# M121B.net
KiCad netlist of a schematic drawn in EAGLE
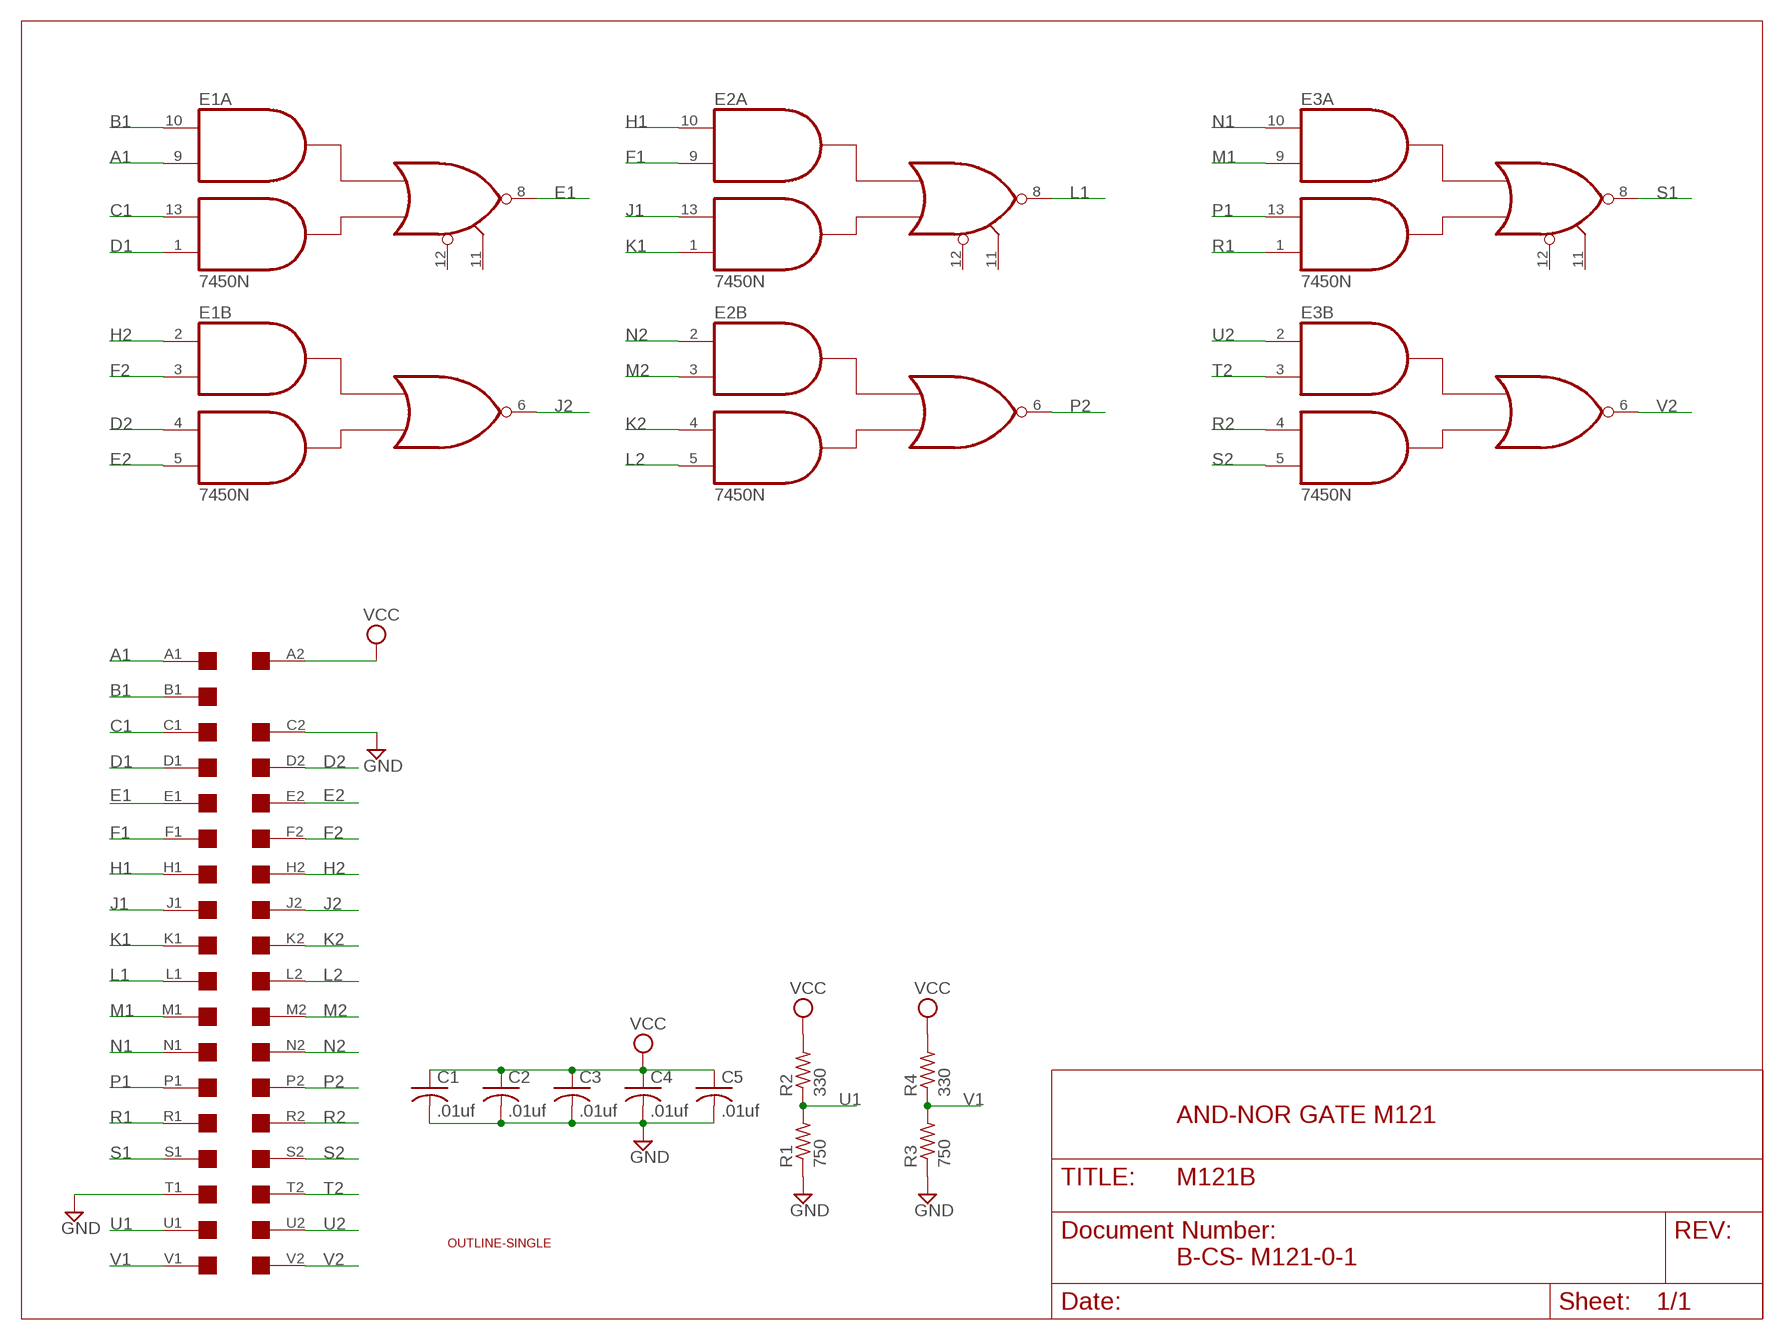
[diagram p0: schematic, sheet 1]

(export (version "E")
  (design (tool "Eeschema 10.0.6"))
  (components
    (comp (ref "C1")
      (value ".01uf")
      (footprint "eagle-import:C050-025X075")
      (libsource (lib "eagle-import") (part "C-US050-025X075"))
    )
    (comp (ref "C2")
      (value ".01uf")
      (footprint "eagle-import:C050-025X075")
      (libsource (lib "eagle-import") (part "C-US050-025X075"))
    )
    (comp (ref "C3")
      (value ".01uf")
      (footprint "eagle-import:C050-025X075")
      (libsource (lib "eagle-import") (part "C-US050-025X075"))
    )
    (comp (ref "C4")
      (value ".01uf")
      (footprint "eagle-import:C050-025X075")
      (libsource (lib "eagle-import") (part "C-US050-025X075"))
    )
    (comp (ref "C5")
      (value ".01uf")
      (footprint "eagle-import:C050-025X075")
      (libsource (lib "eagle-import") (part "C-US050-025X075"))
    )
    (comp (ref "E1")
      (value "7450N")
      (footprint "eagle-import:DIL14")
      (libsource (lib "eagle-import") (part "7450N"))
    )
    (comp (ref "E2")
      (value "7450N")
      (footprint "eagle-import:DIL14")
      (libsource (lib "eagle-import") (part "7450N"))
    )
    (comp (ref "E3")
      (value "7450N")
      (footprint "eagle-import:DIL14")
      (libsource (lib "eagle-import") (part "7450N"))
    )
    (comp (ref "R1")
      (value "750")
      (footprint "eagle-import:0207_10")
      (libsource (lib "eagle-import") (part "R-US_0207/10"))
    )
    (comp (ref "R2")
      (value "330")
      (footprint "eagle-import:0207_10")
      (libsource (lib "eagle-import") (part "R-US_0207/10"))
    )
    (comp (ref "R3")
      (value "750")
      (footprint "eagle-import:0207_10")
      (libsource (lib "eagle-import") (part "R-US_0207/10"))
    )
    (comp (ref "R4")
      (value "330")
      (footprint "eagle-import:0207_10")
      (libsource (lib "eagle-import") (part "R-US_0207/10"))
    )
    (comp (ref "U$1")
      (value "OUTLINE-SINGLE")
      (footprint "eagle-import:SINGLE")
      (libsource (lib "eagle-import") (part "OUTLINE-SINGLE"))
    )
    (comp (ref "U$4")
      (value "SINGLE")
      (footprint "eagle-import:EDGE-CON2")
      (libsource (lib "eagle-import") (part "SINGLE"))
    )
  )
  (nets
    (net (code "1") (name "/A1") (class "Default")
      (node (ref "E1") (pin "9") (pinfunction "I2_9") (pintype "input"))
      (node (ref "U$4") (pin "A1") (pinfunction "1_A1") (pintype "bidirectional"))
    )
    (net (code "2") (name "/B1") (class "Default")
      (node (ref "E1") (pin "10") (pinfunction "I1_10") (pintype "input"))
      (node (ref "U$4") (pin "B1") (pinfunction "1_B1") (pintype "bidirectional"))
    )
    (net (code "3") (name "/C1") (class "Default")
      (node (ref "E1") (pin "13") (pinfunction "I3_13") (pintype "input"))
      (node (ref "U$4") (pin "C1") (pinfunction "1_C1") (pintype "bidirectional"))
    )
    (net (code "4") (name "/D1") (class "Default")
      (node (ref "E1") (pin "1") (pinfunction "I4_1") (pintype "input"))
      (node (ref "U$4") (pin "D1") (pinfunction "1_D1") (pintype "bidirectional"))
    )
    (net (code "5") (name "/D2") (class "Default")
      (node (ref "E1") (pin "4") (pinfunction "I3_4") (pintype "input"))
      (node (ref "U$4") (pin "D2") (pinfunction "1_D2") (pintype "bidirectional"))
    )
    (net (code "6") (name "/E1") (class "Default")
      (node (ref "E1") (pin "8") (pinfunction "O_8") (pintype "output"))
      (node (ref "U$4") (pin "E1") (pinfunction "1_E1") (pintype "bidirectional"))
    )
    (net (code "7") (name "/E2") (class "Default")
      (node (ref "E1") (pin "5") (pinfunction "I4_5") (pintype "input"))
      (node (ref "U$4") (pin "E2") (pinfunction "1_E2") (pintype "bidirectional"))
    )
    (net (code "8") (name "/F1") (class "Default")
      (node (ref "E2") (pin "9") (pinfunction "I2_9") (pintype "input"))
      (node (ref "U$4") (pin "F1") (pinfunction "1_F1") (pintype "bidirectional"))
    )
    (net (code "9") (name "/F2") (class "Default")
      (node (ref "E1") (pin "3") (pinfunction "I2_3") (pintype "input"))
      (node (ref "U$4") (pin "F2") (pinfunction "1_F2") (pintype "bidirectional"))
    )
    (net (code "10") (name "/H1") (class "Default")
      (node (ref "E2") (pin "10") (pinfunction "I1_10") (pintype "input"))
      (node (ref "U$4") (pin "H1") (pinfunction "1_H1") (pintype "bidirectional"))
    )
    (net (code "11") (name "/H2") (class "Default")
      (node (ref "E1") (pin "2") (pinfunction "I1_2") (pintype "input"))
      (node (ref "U$4") (pin "H2") (pinfunction "1_H2") (pintype "bidirectional"))
    )
    (net (code "12") (name "/J1") (class "Default")
      (node (ref "E2") (pin "13") (pinfunction "I3_13") (pintype "input"))
      (node (ref "U$4") (pin "J1") (pinfunction "1_J1") (pintype "bidirectional"))
    )
    (net (code "13") (name "/J2") (class "Default")
      (node (ref "E1") (pin "6") (pinfunction "O_6") (pintype "output"))
      (node (ref "U$4") (pin "J2") (pinfunction "1_J2") (pintype "bidirectional"))
    )
    (net (code "14") (name "/K1") (class "Default")
      (node (ref "E2") (pin "1") (pinfunction "I4_1") (pintype "input"))
      (node (ref "U$4") (pin "K1") (pinfunction "1_K1") (pintype "bidirectional"))
    )
    (net (code "15") (name "/K2") (class "Default")
      (node (ref "E2") (pin "4") (pinfunction "I3_4") (pintype "input"))
      (node (ref "U$4") (pin "K2") (pinfunction "1_K2") (pintype "bidirectional"))
    )
    (net (code "16") (name "/L1") (class "Default")
      (node (ref "E2") (pin "8") (pinfunction "O_8") (pintype "output"))
      (node (ref "U$4") (pin "L1") (pinfunction "1_L1") (pintype "bidirectional"))
    )
    (net (code "17") (name "/L2") (class "Default")
      (node (ref "E2") (pin "5") (pinfunction "I4_5") (pintype "input"))
      (node (ref "U$4") (pin "L2") (pinfunction "1_L2") (pintype "bidirectional"))
    )
    (net (code "18") (name "/M1") (class "Default")
      (node (ref "E3") (pin "9") (pinfunction "I2_9") (pintype "input"))
      (node (ref "U$4") (pin "M1") (pinfunction "1_M1") (pintype "bidirectional"))
    )
    (net (code "19") (name "/M2") (class "Default")
      (node (ref "E2") (pin "3") (pinfunction "I2_3") (pintype "input"))
      (node (ref "U$4") (pin "M2") (pinfunction "1_M2") (pintype "bidirectional"))
    )
    (net (code "20") (name "/N1") (class "Default")
      (node (ref "E3") (pin "10") (pinfunction "I1_10") (pintype "input"))
      (node (ref "U$4") (pin "N1") (pinfunction "1_N1") (pintype "bidirectional"))
    )
    (net (code "21") (name "/N2") (class "Default")
      (node (ref "E2") (pin "2") (pinfunction "I1_2") (pintype "input"))
      (node (ref "U$4") (pin "N2") (pinfunction "1_N2") (pintype "bidirectional"))
    )
    (net (code "22") (name "/P1") (class "Default")
      (node (ref "E3") (pin "13") (pinfunction "I3_13") (pintype "input"))
      (node (ref "U$4") (pin "P1") (pinfunction "1_P1") (pintype "bidirectional"))
    )
    (net (code "23") (name "/P2") (class "Default")
      (node (ref "E2") (pin "6") (pinfunction "O_6") (pintype "output"))
      (node (ref "U$4") (pin "P2") (pinfunction "1_P2") (pintype "bidirectional"))
    )
    (net (code "24") (name "/R1") (class "Default")
      (node (ref "E3") (pin "1") (pinfunction "I4_1") (pintype "input"))
      (node (ref "U$4") (pin "R1") (pinfunction "1_R1") (pintype "bidirectional"))
    )
    (net (code "25") (name "/R2") (class "Default")
      (node (ref "E3") (pin "4") (pinfunction "I3_4") (pintype "input"))
      (node (ref "U$4") (pin "R2") (pinfunction "1_R2") (pintype "bidirectional"))
    )
    (net (code "26") (name "/S1") (class "Default")
      (node (ref "E3") (pin "8") (pinfunction "O_8") (pintype "output"))
      (node (ref "U$4") (pin "S1") (pinfunction "1_S1") (pintype "bidirectional"))
    )
    (net (code "27") (name "/S2") (class "Default")
      (node (ref "E3") (pin "5") (pinfunction "I4_5") (pintype "input"))
      (node (ref "U$4") (pin "S2") (pinfunction "1_S2") (pintype "bidirectional"))
    )
    (net (code "28") (name "/T2") (class "Default")
      (node (ref "E3") (pin "3") (pinfunction "I2_3") (pintype "input"))
      (node (ref "U$4") (pin "T2") (pinfunction "1_T2") (pintype "bidirectional"))
    )
    (net (code "29") (name "/U1") (class "Default")
      (node (ref "R1") (pin "2") (pinfunction "2_2") (pintype "passive"))
      (node (ref "R2") (pin "1") (pinfunction "1_1") (pintype "passive"))
      (node (ref "U$4") (pin "U1") (pinfunction "1_U1") (pintype "bidirectional"))
    )
    (net (code "30") (name "/U2") (class "Default")
      (node (ref "E3") (pin "2") (pinfunction "I1_2") (pintype "input"))
      (node (ref "U$4") (pin "U2") (pinfunction "1_U2") (pintype "bidirectional"))
    )
    (net (code "31") (name "/V1") (class "Default")
      (node (ref "R3") (pin "2") (pinfunction "2_2") (pintype "passive"))
      (node (ref "R4") (pin "1") (pinfunction "1_1") (pintype "passive"))
      (node (ref "U$4") (pin "V1") (pinfunction "1_V1") (pintype "bidirectional"))
    )
    (net (code "32") (name "/V2") (class "Default")
      (node (ref "E3") (pin "6") (pinfunction "O_6") (pintype "output"))
      (node (ref "U$4") (pin "V2") (pinfunction "1_V2") (pintype "bidirectional"))
    )
    (net (code "33") (name "GND") (class "Default")
      (node (ref "C1") (pin "2") (pinfunction "2_2") (pintype "passive"))
      (node (ref "C2") (pin "2") (pinfunction "2_2") (pintype "passive"))
      (node (ref "C3") (pin "2") (pinfunction "2_2") (pintype "passive"))
      (node (ref "C4") (pin "2") (pinfunction "2_2") (pintype "passive"))
      (node (ref "C5") (pin "2") (pinfunction "2_2") (pintype "passive"))
      (node (ref "R1") (pin "1") (pinfunction "1_1") (pintype "passive"))
      (node (ref "R3") (pin "1") (pinfunction "1_1") (pintype "passive"))
      (node (ref "U$4") (pin "C2") (pinfunction "1_C2") (pintype "bidirectional"))
      (node (ref "U$4") (pin "T1") (pinfunction "1_T1") (pintype "bidirectional"))
    )
    (net (code "34") (name "VCC") (class "Default")
      (node (ref "C1") (pin "1") (pinfunction "1_1") (pintype "passive"))
      (node (ref "C2") (pin "1") (pinfunction "1_1") (pintype "passive"))
      (node (ref "C3") (pin "1") (pinfunction "1_1") (pintype "passive"))
      (node (ref "C4") (pin "1") (pinfunction "1_1") (pintype "passive"))
      (node (ref "C5") (pin "1") (pinfunction "1_1") (pintype "passive"))
      (node (ref "R2") (pin "2") (pinfunction "2_2") (pintype "passive"))
      (node (ref "R4") (pin "2") (pinfunction "2_2") (pintype "passive"))
      (node (ref "U$4") (pin "A2") (pinfunction "1_A2") (pintype "bidirectional"))
    )
    (net (code "35") (name "unconnected-(E1A-I5-Pad12)") (class "Default")
      (node (ref "E1") (pin "12") (pinfunction "I5_12") (pintype "passive"))
    )
    (net (code "36") (name "unconnected-(E1A-I6-Pad11)") (class "Default")
      (node (ref "E1") (pin "11") (pinfunction "I6_11") (pintype "passive"))
    )
    (net (code "37") (name "unconnected-(E2A-I5-Pad12)") (class "Default")
      (node (ref "E2") (pin "12") (pinfunction "I5_12") (pintype "passive"))
    )
    (net (code "38") (name "unconnected-(E2A-I6-Pad11)") (class "Default")
      (node (ref "E2") (pin "11") (pinfunction "I6_11") (pintype "passive"))
    )
    (net (code "39") (name "unconnected-(E3A-I5-Pad12)") (class "Default")
      (node (ref "E3") (pin "12") (pinfunction "I5_12") (pintype "passive"))
    )
    (net (code "40") (name "unconnected-(E3A-I6-Pad11)") (class "Default")
      (node (ref "E3") (pin "11") (pinfunction "I6_11") (pintype "passive"))
    )
  )
)
